# Schematic.net
KiCad netlist of a schematic drawn in EAGLE
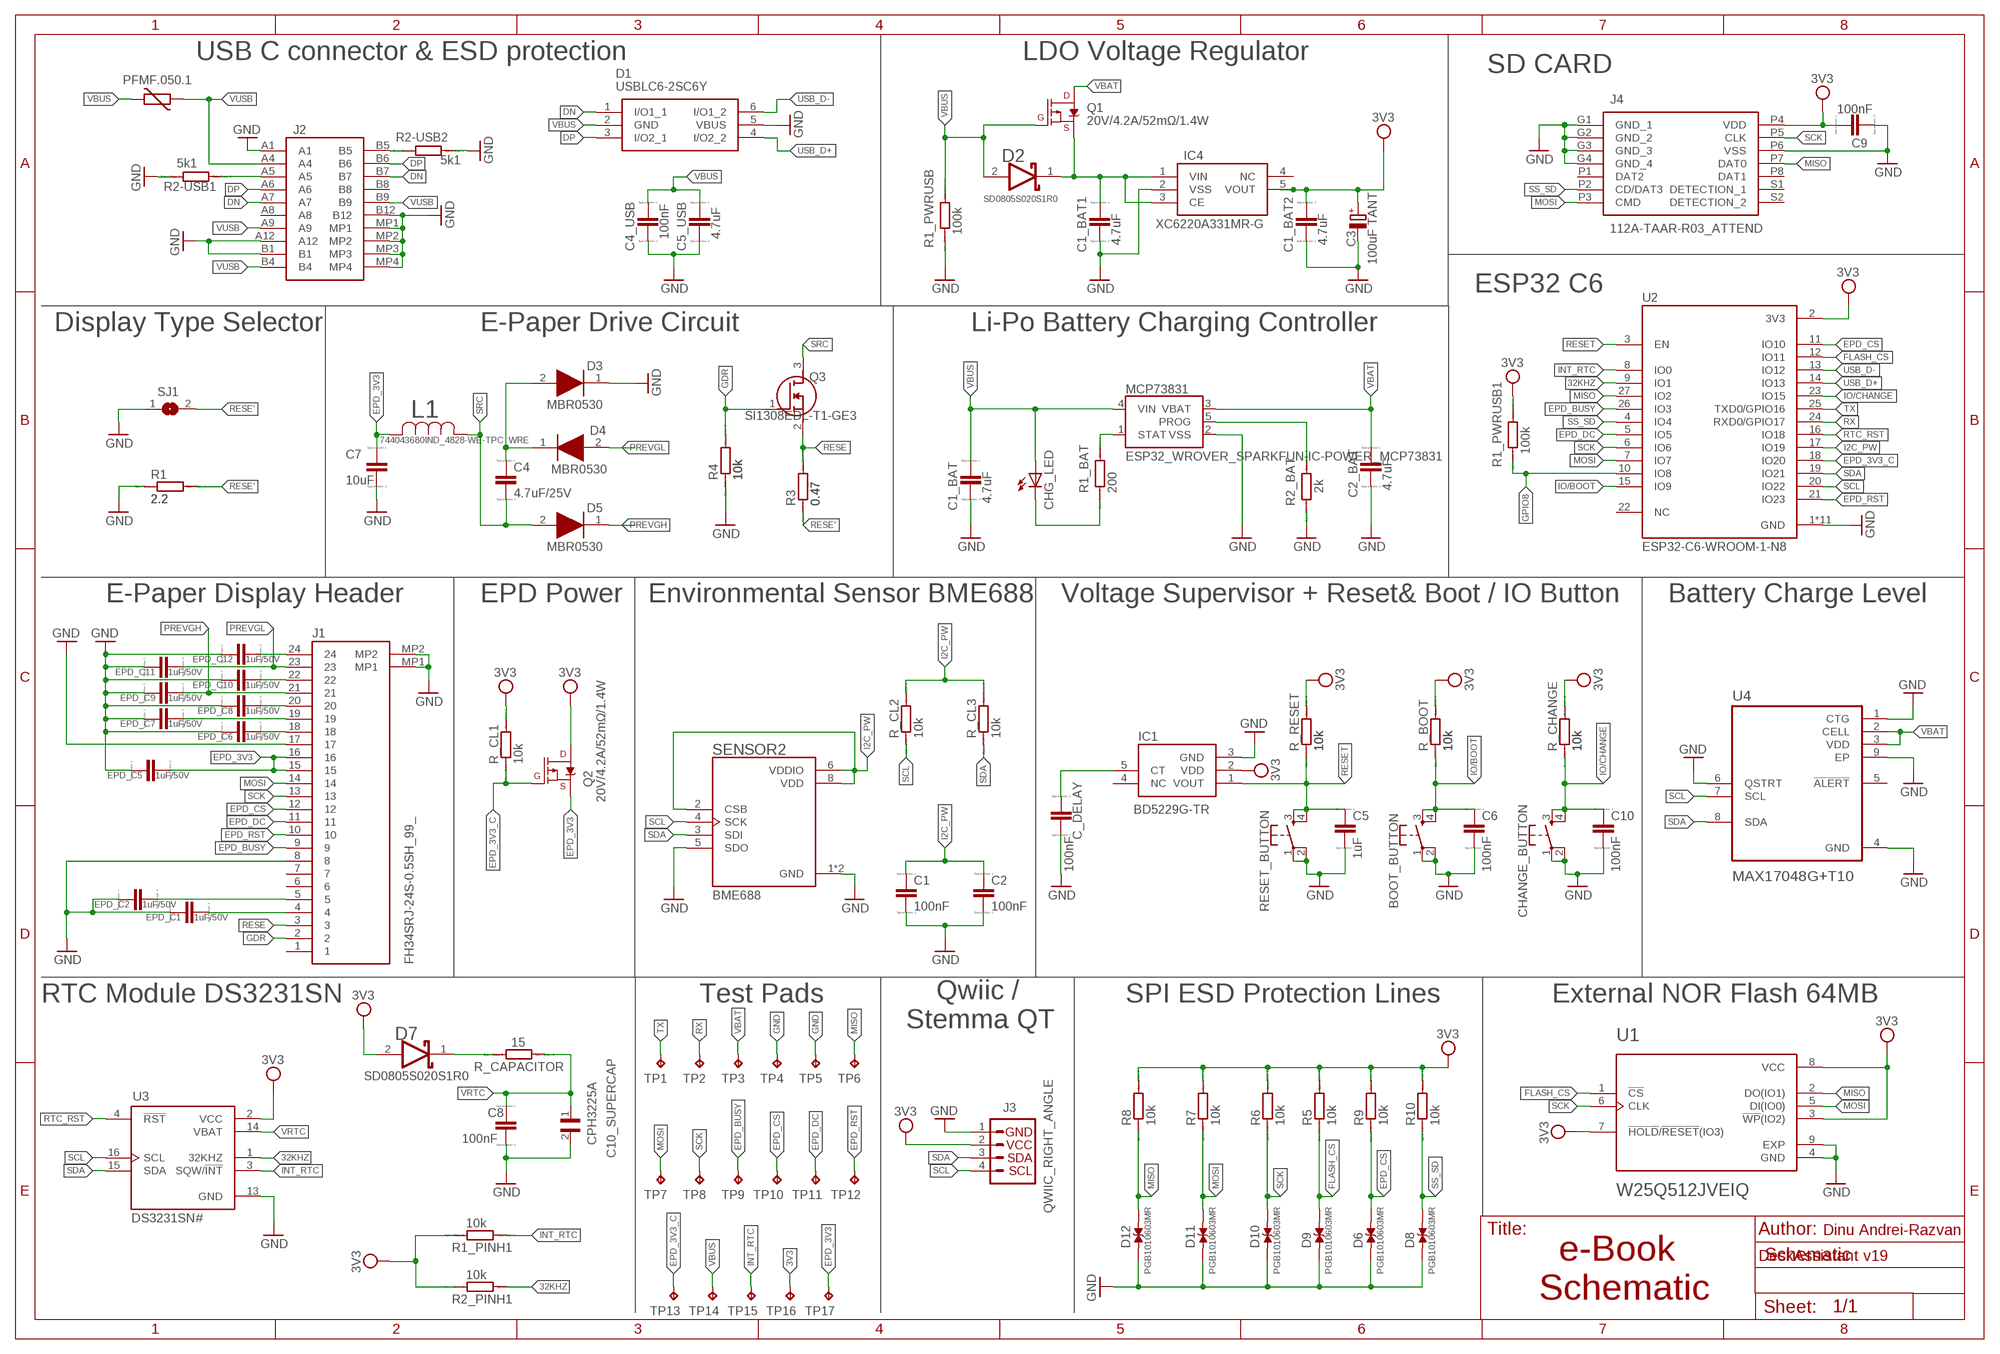
[diagram p0: schematic, sheet 1]

(export (version "E")
  (design (tool "Eeschema 10.0.6"))
  (components
    (comp (ref "BOOT_BUTTON")
      (value "BUTTON_CUSYOMV1")
      (footprint "eagle-import:MYBUTTON")
      (libsource (lib "eagle-import") (part "BUTTON_CUSYOMV1"))
    )
    (comp (ref "C1")
      (value "100nF")
      (footprint "eagle-import:EAGLE-LTSPICE_C0402")
      (libsource (lib "eagle-import") (part "EAGLE-LTSPICE_CC0402"))
    )
    (comp (ref "C1_BAT")
      (value "4.7uF")
      (footprint "eagle-import:EAGLE-LTSPICE_C0402")
      (libsource (lib "eagle-import") (part "EAGLE-LTSPICE_CC0402"))
    )
    (comp (ref "C1_BAT1")
      (value "4.7uF")
      (footprint "eagle-import:EAGLE-LTSPICE_C0402")
      (libsource (lib "eagle-import") (part "EAGLE-LTSPICE_CC0402"))
    )
    (comp (ref "C1_BAT2")
      (value "4.7uF")
      (footprint "eagle-import:EAGLE-LTSPICE_C0402")
      (libsource (lib "eagle-import") (part "EAGLE-LTSPICE_CC0402"))
    )
    (comp (ref "C2")
      (value "100nF")
      (footprint "eagle-import:EAGLE-LTSPICE_C0402")
      (libsource (lib "eagle-import") (part "EAGLE-LTSPICE_CC0402"))
    )
    (comp (ref "C2_BAT")
      (value "4.7uF")
      (footprint "eagle-import:EAGLE-LTSPICE_C0402")
      (libsource (lib "eagle-import") (part "EAGLE-LTSPICE_CC0402"))
    )
    (comp (ref "C3")
      (value "100uF TANT")
      (footprint "eagle-import:RCL_CT3528")
      (libsource (lib "eagle-import") (part "RCL_CPOL-EUCT3528"))
    )
    (comp (ref "C4")
      (value "4.7uF/25V")
      (footprint "eagle-import:EAGLE-LTSPICE_C0402")
      (libsource (lib "eagle-import") (part "EAGLE-LTSPICE_CC0402"))
    )
    (comp (ref "C4_USB")
      (value "100nF")
      (footprint "eagle-import:ESP32_WROVER_EAGLE-LTSPICE_C0402")
      (libsource (lib "eagle-import") (part "ESP32_WROVER_EAGLE-LTSPICE_CC0402"))
    )
    (comp (ref "C5")
      (value "1uF")
      (footprint "eagle-import:EAGLE-LTSPICE_C0402")
      (libsource (lib "eagle-import") (part "EAGLE-LTSPICE_CC0402"))
    )
    (comp (ref "C5_USB")
      (value "4.7uF")
      (footprint "eagle-import:ESP32_WROVER_EAGLE-LTSPICE_C0402")
      (libsource (lib "eagle-import") (part "ESP32_WROVER_EAGLE-LTSPICE_CC0402"))
    )
    (comp (ref "C6")
      (value "100nF")
      (footprint "eagle-import:EAGLE-LTSPICE_C0402")
      (libsource (lib "eagle-import") (part "EAGLE-LTSPICE_CC0402"))
    )
    (comp (ref "C7")
      (value "10uF")
      (footprint "eagle-import:EAGLE-LTSPICE_C0402")
      (libsource (lib "eagle-import") (part "EAGLE-LTSPICE_CC0402"))
    )
    (comp (ref "C8")
      (value "100nF")
      (footprint "eagle-import:EAGLE-LTSPICE_C0402")
      (libsource (lib "eagle-import") (part "EAGLE-LTSPICE_CC0402"))
    )
    (comp (ref "C9")
      (value "100nF")
      (footprint "eagle-import:ESP32_WROVER_EAGLE-LTSPICE_C0402")
      (libsource (lib "eagle-import") (part "ESP32_WROVER_EAGLE-LTSPICE_CC0402"))
    )
    (comp (ref "C10")
      (value "100nF")
      (footprint "eagle-import:EAGLE-LTSPICE_C0402")
      (libsource (lib "eagle-import") (part "EAGLE-LTSPICE_CC0402"))
    )
    (comp (ref "C10_SUPERCAP")
      (value "CPH3225A")
      (footprint "eagle-import:CAPCP3225X100N")
      (fields (field (name "MF") "Seiko Instruments"))
      (libsource (lib "eagle-import") (part "CPH3225A"))
    )
    (comp (ref "CHANGE_BUTTON")
      (value "BUTTON_CUSYOMV1")
      (footprint "eagle-import:MYBUTTON")
      (libsource (lib "eagle-import") (part "BUTTON_CUSYOMV1"))
    )
    (comp (ref "CHG_LED")
      (value "ADAFRUIT_LEDCHIP-LED0603")
      (footprint "eagle-import:ADAFRUIT_CHIP-LED0603")
      (libsource (lib "eagle-import") (part "ADAFRUIT_LEDCHIP-LED0603"))
    )
    (comp (ref "C_DELAY")
      (value "100nF")
      (footprint "eagle-import:EAGLE-LTSPICE_C0402")
      (libsource (lib "eagle-import") (part "EAGLE-LTSPICE_CC0402"))
    )
    (comp (ref "D1")
      (value "USBLC6-2SC6Y")
      (footprint "eagle-import:SOT95P280X145-6N")
      (fields (field (name "MF") "STMicroelectronics"))
      (libsource (lib "eagle-import") (part "USBLC6-2SC6Y"))
    )
    (comp (ref "D2")
      (value "ESP32_WROVER_AVX---SD0805S020S1R0_AVX_SD0805S020S1R0_0_0AVX_SD0805S020S1R0_0_0")
      (footprint "eagle-import:ESP32_WROVER_AVX---SD0805S020S1R0_AVX_SD0805S020S1R0_0")
      (fields
        (field (name "DIGIKEY_PART_NUMBER") "478-7800-1-ND")
        (field (name "MF") "AVX")
        (field (name "MOUSER_PART_NUMBER") "581-SD0805S020S1R0")
      )
      (libsource (lib "eagle-import") (part "ESP32_WROVER_AVX---SD0805S020S1R0_AVX_SD0805S020S1R0_0_0AVX_SD0805S020S1R0_0_0"))
    )
    (comp (ref "D3")
      (value "MBR0530")
      (footprint "eagle-import:SOD3716X135N")
      (fields (field (name "MF") "ON Semiconductor"))
      (libsource (lib "eagle-import") (part "MBR0530"))
    )
    (comp (ref "D4")
      (value "MBR0530")
      (footprint "eagle-import:SOD3716X135N")
      (fields (field (name "MF") "ON Semiconductor"))
      (libsource (lib "eagle-import") (part "MBR0530"))
    )
    (comp (ref "D5")
      (value "MBR0530")
      (footprint "eagle-import:SOD3716X135N")
      (fields (field (name "MF") "ON Semiconductor"))
      (libsource (lib "eagle-import") (part "MBR0530"))
    )
    (comp (ref "D6")
      (value "PGB1010603MR")
      (footprint "eagle-import:DIOC1608X36N")
      (fields (field (name "MF") "Littelfuse Inc."))
      (libsource (lib "eagle-import") (part "PGB1010603MR"))
    )
    (comp (ref "D7")
      (value "ESP32_WROVER_AVX---SD0805S020S1R0_AVX_SD0805S020S1R0_0_0AVX_SD0805S020S1R0_0_0")
      (footprint "eagle-import:ESP32_WROVER_AVX---SD0805S020S1R0_AVX_SD0805S020S1R0_0")
      (fields
        (field (name "DIGIKEY_PART_NUMBER") "478-7800-1-ND")
        (field (name "MF") "AVX")
        (field (name "MOUSER_PART_NUMBER") "581-SD0805S020S1R0")
      )
      (libsource (lib "eagle-import") (part "ESP32_WROVER_AVX---SD0805S020S1R0_AVX_SD0805S020S1R0_0_0AVX_SD0805S020S1R0_0_0"))
    )
    (comp (ref "D8")
      (value "PGB1010603MR")
      (footprint "eagle-import:DIOC1608X36N")
      (fields (field (name "MF") "Littelfuse Inc."))
      (libsource (lib "eagle-import") (part "PGB1010603MR"))
    )
    (comp (ref "D9")
      (value "PGB1010603MR")
      (footprint "eagle-import:DIOC1608X36N")
      (fields (field (name "MF") "Littelfuse Inc."))
      (libsource (lib "eagle-import") (part "PGB1010603MR"))
    )
    (comp (ref "D10")
      (value "PGB1010603MR")
      (footprint "eagle-import:DIOC1608X36N")
      (fields (field (name "MF") "Littelfuse Inc."))
      (libsource (lib "eagle-import") (part "PGB1010603MR"))
    )
    (comp (ref "D11")
      (value "PGB1010603MR")
      (footprint "eagle-import:DIOC1608X36N")
      (fields (field (name "MF") "Littelfuse Inc."))
      (libsource (lib "eagle-import") (part "PGB1010603MR"))
    )
    (comp (ref "D12")
      (value "PGB1010603MR")
      (footprint "eagle-import:DIOC1608X36N")
      (fields (field (name "MF") "Littelfuse Inc."))
      (libsource (lib "eagle-import") (part "PGB1010603MR"))
    )
    (comp (ref "EPD_C1")
      (value "1uF/50V")
      (footprint "eagle-import:EAGLE-LTSPICE_C0402")
      (libsource (lib "eagle-import") (part "EAGLE-LTSPICE_CC0402"))
    )
    (comp (ref "EPD_C2")
      (value "1uF/50V")
      (footprint "eagle-import:EAGLE-LTSPICE_C0402")
      (libsource (lib "eagle-import") (part "EAGLE-LTSPICE_CC0402"))
    )
    (comp (ref "EPD_C5")
      (value "1uF/50V")
      (footprint "eagle-import:EAGLE-LTSPICE_C0402")
      (libsource (lib "eagle-import") (part "EAGLE-LTSPICE_CC0402"))
    )
    (comp (ref "EPD_C6")
      (value "1uF/50V")
      (footprint "eagle-import:EAGLE-LTSPICE_C0402")
      (libsource (lib "eagle-import") (part "EAGLE-LTSPICE_CC0402"))
    )
    (comp (ref "EPD_C7")
      (value "1uF/50V")
      (footprint "eagle-import:EAGLE-LTSPICE_C0402")
      (libsource (lib "eagle-import") (part "EAGLE-LTSPICE_CC0402"))
    )
    (comp (ref "EPD_C8")
      (value "1uF/50V")
      (footprint "eagle-import:EAGLE-LTSPICE_C0402")
      (libsource (lib "eagle-import") (part "EAGLE-LTSPICE_CC0402"))
    )
    (comp (ref "EPD_C9")
      (value "1uF/50V")
      (footprint "eagle-import:EAGLE-LTSPICE_C0402")
      (libsource (lib "eagle-import") (part "EAGLE-LTSPICE_CC0402"))
    )
    (comp (ref "EPD_C10")
      (value "1uF/50V")
      (footprint "eagle-import:EAGLE-LTSPICE_C0402")
      (libsource (lib "eagle-import") (part "EAGLE-LTSPICE_CC0402"))
    )
    (comp (ref "EPD_C11")
      (value "1uF/50V")
      (footprint "eagle-import:EAGLE-LTSPICE_C0402")
      (libsource (lib "eagle-import") (part "EAGLE-LTSPICE_CC0402"))
    )
    (comp (ref "EPD_C12")
      (value "1uF/50V")
      (footprint "eagle-import:EAGLE-LTSPICE_C0402")
      (libsource (lib "eagle-import") (part "EAGLE-LTSPICE_CC0402"))
    )
    (comp (ref "IC1")
      (value "BD5229G-TR")
      (footprint "eagle-import:SOT95P280X125-5N")
      (fields (field (name "MOUSER_PART_NUMBER") "755-BD5229G-TR"))
      (libsource (lib "eagle-import") (part "BD5229G-TR"))
    )
    (comp (ref "IC4")
      (value "XC6220A331MR-G")
      (footprint "eagle-import:SOT95P280X120-5N")
      (fields (field (name "MOUSER_PART_NUMBER") "865-XC6220A331MR-G"))
      (libsource (lib "eagle-import") (part "XC6220A331MR-G"))
    )
    (comp (ref "J1")
      (value "FH34SRJ-24S-0.5SH_99_")
      (footprint "eagle-import:FH34SRJ24S05SH99")
      (fields
        (field (name "MANUFACTURER_PART_NUMBER") "FH34SRJ-24S-0.5SH(99)")
        (field (name "MOUSER_PART_NUMBER") "798-FH34SRJ24S05SH99")
      )
      (libsource (lib "eagle-import") (part "FH34SRJ-24S-0.5SH_99_"))
    )
    (comp (ref "J2")
      (value "SAMACSYS_PARTS_USB4110-GF-A")
      (footprint "eagle-import:SAMACSYS_PARTS_USB4110GFA")
      (fields
        (field (name "MANUFACTURER_PART_NUMBER") "USB4110-GF-A")
        (field (name "MOUSER_PART_NUMBER") "640-USB4110-GF-A")
      )
      (libsource (lib "eagle-import") (part "SAMACSYS_PARTS_USB4110-GF-A"))
    )
    (comp (ref "J3")
      (value "QWIIC_RIGHT_ANGLE")
      (footprint "eagle-import:JST04_1MM_RA")
      (libsource (lib "eagle-import") (part "QWIIC_CONNECTORJS-1MM"))
    )
    (comp (ref "J4")
      (value "112A-TAAR-R03_ATTEND")
      (footprint "eagle-import:112ATAARR03ATTEND")
      (fields (field (name "MANUFACTURER_PART_NUMBER") "112A-TAAR-R03 ATTEND"))
      (libsource (lib "eagle-import") (part "112A-TAAR-R03_ATTEND"))
    )
    (comp (ref "L1")
      (value "744043680IND_4828-WE-TPC_WRE")
      (footprint "eagle-import:IND_4828-WE-TPC_WRE")
      (fields
        (field (name "MANUFACTURER_PART_NUMBER") "744043680")
        (field (name "COPYRIGHT") "Copyright (C) 2024 Ultra Librarian. All rights reserved.")
      )
      (libsource (lib "eagle-import") (part "744043680IND_4828-WE-TPC_WRE"))
    )
    (comp (ref "MCP73831")
      (value "ESP32_WROVER_SPARKFUN-IC-POWER_MCP73831")
      (footprint "eagle-import:ESP32_WROVER_SPARKFUN-IC-POWER_SOT23-5")
      (libsource (lib "eagle-import") (part "ESP32_WROVER_SPARKFUN-IC-POWER_MCP73831"))
    )
    (comp (ref "PFMF.050.1")
      (value "ESP32C6_VARISTORCN1812")
      (footprint "eagle-import:ESP32C6_VARISTOR_CT_CN1812")
      (libsource (lib "eagle-import") (part "ESP32C6_VARISTORCN1812"))
    )
    (comp (ref "Q1")
      (value "20V/4.2A/52mΩ/1.4W")
      (footprint "eagle-import:ESP32_WROVER_SPARKFUN-DISCRETESEMI_SOT23-3")
      (libsource (lib "eagle-import") (part "ESP32_WROVER_SPARKFUN-DISCRETESEMI_MOSFET_PCH-DMG2305UX-7"))
    )
    (comp (ref "Q2")
      (value "20V/4.2A/52mΩ/1.4W")
      (footprint "eagle-import:ESP32_WROVER_SPARKFUN-DISCRETESEMI_SOT23-3")
      (libsource (lib "eagle-import") (part "ESP32_WROVER_SPARKFUN-DISCRETESEMI_MOSFET_PCH-DMG2305UX-7"))
    )
    (comp (ref "Q3")
      (value "SI1308EDL-T1-GE3")
      (footprint "eagle-import:SOT65P210X110-3N")
      (fields (field (name "MF") "Vishay Siliconix"))
      (libsource (lib "eagle-import") (part "SI1308EDL-T1-GE3"))
    )
    (comp (ref "R1")
      (value "2.2")
      (footprint "eagle-import:ESP32_WROVER_EAGLE-LTSPICE_R0402")
      (libsource (lib "eagle-import") (part "ESP32_WROVER_EAGLE-LTSPICE_RR0402"))
    )
    (comp (ref "R1_BAT")
      (value "200")
      (footprint "eagle-import:ESP32_WROVER_EAGLE-LTSPICE_R0402")
      (libsource (lib "eagle-import") (part "ESP32_WROVER_EAGLE-LTSPICE_RR0402"))
    )
    (comp (ref "R1_PINH1")
      (value "10k")
      (footprint "eagle-import:ESP32_WROVER_EAGLE-LTSPICE_R0402")
      (libsource (lib "eagle-import") (part "ESP32_WROVER_EAGLE-LTSPICE_RR0402"))
    )
    (comp (ref "R1_PWRUSB")
      (value "100k")
      (footprint "eagle-import:ESP32_WROVER_EAGLE-LTSPICE_R0402")
      (libsource (lib "eagle-import") (part "ESP32_WROVER_EAGLE-LTSPICE_RR0402"))
    )
    (comp (ref "R1_PWRUSB1")
      (value "100k")
      (footprint "eagle-import:ESP32_WROVER_EAGLE-LTSPICE_R0402")
      (libsource (lib "eagle-import") (part "ESP32_WROVER_EAGLE-LTSPICE_RR0402"))
    )
    (comp (ref "R2-USB1")
      (value "5k1")
      (footprint "eagle-import:ESP32_WROVER_EAGLE-LTSPICE_R0402")
      (libsource (lib "eagle-import") (part "ESP32_WROVER_EAGLE-LTSPICE_RR0402"))
    )
    (comp (ref "R2-USB2")
      (value "5k1")
      (footprint "eagle-import:ESP32_WROVER_EAGLE-LTSPICE_R0402")
      (libsource (lib "eagle-import") (part "ESP32_WROVER_EAGLE-LTSPICE_RR0402"))
    )
    (comp (ref "R2_BAT")
      (value "2k")
      (footprint "eagle-import:ESP32_WROVER_EAGLE-LTSPICE_R0402")
      (libsource (lib "eagle-import") (part "ESP32_WROVER_EAGLE-LTSPICE_RR0402"))
    )
    (comp (ref "R2_PINH1")
      (value "10k")
      (footprint "eagle-import:ESP32_WROVER_EAGLE-LTSPICE_R0402")
      (libsource (lib "eagle-import") (part "ESP32_WROVER_EAGLE-LTSPICE_RR0402"))
    )
    (comp (ref "R3")
      (value "0.47")
      (footprint "eagle-import:ESP32_WROVER_EAGLE-LTSPICE_R0402")
      (libsource (lib "eagle-import") (part "ESP32_WROVER_EAGLE-LTSPICE_RR0402"))
    )
    (comp (ref "R4")
      (value "10k")
      (footprint "eagle-import:ESP32_WROVER_EAGLE-LTSPICE_R0402")
      (libsource (lib "eagle-import") (part "ESP32_WROVER_EAGLE-LTSPICE_RR0402"))
    )
    (comp (ref "R5")
      (value "10k")
      (footprint "eagle-import:ESP32_WROVER_EAGLE-LTSPICE_R0402")
      (libsource (lib "eagle-import") (part "ESP32_WROVER_EAGLE-LTSPICE_RR0402"))
    )
    (comp (ref "R6")
      (value "10k")
      (footprint "eagle-import:ESP32_WROVER_EAGLE-LTSPICE_R0402")
      (libsource (lib "eagle-import") (part "ESP32_WROVER_EAGLE-LTSPICE_RR0402"))
    )
    (comp (ref "R7")
      (value "10k")
      (footprint "eagle-import:ESP32_WROVER_EAGLE-LTSPICE_R0402")
      (libsource (lib "eagle-import") (part "ESP32_WROVER_EAGLE-LTSPICE_RR0402"))
    )
    (comp (ref "R8")
      (value "10k")
      (footprint "eagle-import:ESP32_WROVER_EAGLE-LTSPICE_R0402")
      (libsource (lib "eagle-import") (part "ESP32_WROVER_EAGLE-LTSPICE_RR0402"))
    )
    (comp (ref "R9")
      (value "10k")
      (footprint "eagle-import:ESP32_WROVER_EAGLE-LTSPICE_R0402")
      (libsource (lib "eagle-import") (part "ESP32_WROVER_EAGLE-LTSPICE_RR0402"))
    )
    (comp (ref "R10")
      (value "10k")
      (footprint "eagle-import:ESP32_WROVER_EAGLE-LTSPICE_R0402")
      (libsource (lib "eagle-import") (part "ESP32_WROVER_EAGLE-LTSPICE_RR0402"))
    )
    (comp (ref "RESET_BUTTON")
      (value "BUTTON_CUSYOMV1")
      (footprint "eagle-import:MYBUTTON")
      (libsource (lib "eagle-import") (part "BUTTON_CUSYOMV1"))
    )
    (comp (ref "R_BOOT")
      (value "10k")
      (footprint "eagle-import:ESP32_WROVER_EAGLE-LTSPICE_R0402")
      (libsource (lib "eagle-import") (part "ESP32_WROVER_EAGLE-LTSPICE_RR0402"))
    )
    (comp (ref "R_CAPACITOR")
      (value "15")
      (footprint "eagle-import:ESP32_WROVER_EAGLE-LTSPICE_R0402")
      (libsource (lib "eagle-import") (part "ESP32_WROVER_EAGLE-LTSPICE_RR0402"))
    )
    (comp (ref "R_CHANGE")
      (value "10k")
      (footprint "eagle-import:ESP32_WROVER_EAGLE-LTSPICE_R0402")
      (libsource (lib "eagle-import") (part "ESP32_WROVER_EAGLE-LTSPICE_RR0402"))
    )
    (comp (ref "R_CL1")
      (value "10k")
      (footprint "eagle-import:ESP32_WROVER_EAGLE-LTSPICE_R0402")
      (libsource (lib "eagle-import") (part "ESP32_WROVER_EAGLE-LTSPICE_RR0402"))
    )
    (comp (ref "R_CL2")
      (value "10k")
      (footprint "eagle-import:ESP32_WROVER_EAGLE-LTSPICE_R0402")
      (libsource (lib "eagle-import") (part "ESP32_WROVER_EAGLE-LTSPICE_RR0402"))
    )
    (comp (ref "R_CL3")
      (value "10k")
      (footprint "eagle-import:ESP32_WROVER_EAGLE-LTSPICE_R0402")
      (libsource (lib "eagle-import") (part "ESP32_WROVER_EAGLE-LTSPICE_RR0402"))
    )
    (comp (ref "R_RESET")
      (value "10k")
      (footprint "eagle-import:ESP32_WROVER_EAGLE-LTSPICE_R0402")
      (libsource (lib "eagle-import") (part "ESP32_WROVER_EAGLE-LTSPICE_RR0402"))
    )
    (comp (ref "SENSOR2")
      (value "ESP32_WROVER_BME680_BME680")
      (footprint "eagle-import:ESP32_WROVER_BME680_PSON80P300X300X100-8N")
      (fields (field (name "MF") "Bosch Sensortec") (field (name "MP") "BME680"))
      (libsource (lib "eagle-import") (part "ESP32_WROVER_BME680_BME680"))
    )
    (comp (ref "SJ1") (value "SJ") (footprint "eagle-import:SJ") (libsource (lib "eagle-import") (part "SJ")))
    (comp (ref "TP1")
      (value "TPTP20R")
      (footprint "eagle-import:TP20R")
      (libsource (lib "eagle-import") (part "TPTP20R"))
    )
    (comp (ref "TP2")
      (value "TPTP20R")
      (footprint "eagle-import:TP20R")
      (libsource (lib "eagle-import") (part "TPTP20R"))
    )
    (comp (ref "TP3")
      (value "TPTP20R")
      (footprint "eagle-import:TP20R")
      (libsource (lib "eagle-import") (part "TPTP20R"))
    )
    (comp (ref "TP4")
      (value "TPTP20R")
      (footprint "eagle-import:TP20R")
      (libsource (lib "eagle-import") (part "TPTP20R"))
    )
    (comp (ref "TP5")
      (value "TPTP20R")
      (footprint "eagle-import:TP20R")
      (libsource (lib "eagle-import") (part "TPTP20R"))
    )
    (comp (ref "TP6")
      (value "TPTP20R")
      (footprint "eagle-import:TP20R")
      (libsource (lib "eagle-import") (part "TPTP20R"))
    )
    (comp (ref "TP7")
      (value "TPTP20R")
      (footprint "eagle-import:TP20R")
      (libsource (lib "eagle-import") (part "TPTP20R"))
    )
    (comp (ref "TP8")
      (value "TPTP20R")
      (footprint "eagle-import:TP20R")
      (libsource (lib "eagle-import") (part "TPTP20R"))
    )
    (comp (ref "TP9")
      (value "TPTP20R")
      (footprint "eagle-import:TP20R")
      (libsource (lib "eagle-import") (part "TPTP20R"))
    )
    (comp (ref "TP10")
      (value "TPTP20R")
      (footprint "eagle-import:TP20R")
      (libsource (lib "eagle-import") (part "TPTP20R"))
    )
    (comp (ref "TP11")
      (value "TPTP20R")
      (footprint "eagle-import:TP20R")
      (libsource (lib "eagle-import") (part "TPTP20R"))
    )
    (comp (ref "TP12")
      (value "TPTP20R")
      (footprint "eagle-import:TP20R")
      (libsource (lib "eagle-import") (part "TPTP20R"))
    )
    (comp (ref "TP13")
      (value "TPTP20R")
      (footprint "eagle-import:TP20R")
      (libsource (lib "eagle-import") (part "TPTP20R"))
    )
    (comp (ref "TP14")
      (value "TPTP20R")
      (footprint "eagle-import:TP20R")
      (libsource (lib "eagle-import") (part "TPTP20R"))
    )
    (comp (ref "TP15")
      (value "TPTP20R")
      (footprint "eagle-import:TP20R")
      (libsource (lib "eagle-import") (part "TPTP20R"))
    )
    (comp (ref "TP16")
      (value "TPTP20R")
      (footprint "eagle-import:TP20R")
      (libsource (lib "eagle-import") (part "TPTP20R"))
    )
    (comp (ref "TP17")
      (value "TPTP20R")
      (footprint "eagle-import:TP20R")
      (libsource (lib "eagle-import") (part "TPTP20R"))
    )
    (comp (ref "U1")
      (value "W25Q512JVEIQ")
      (footprint "eagle-import:SON127P600X800X80-9N")
      (fields (field (name "MF") "Winbond Electronics"))
      (libsource (lib "eagle-import") (part "W25Q512JVEIQ"))
    )
    (comp (ref "U2")
      (value "ESP32-C6-WROOM-1-N8")
      (footprint "eagle-import:XCVR_ESP32-C6-WROOM-1-N8")
      (fields (field (name "MF") "Espressif Systems"))
      (libsource (lib "eagle-import") (part "ESP32-C6-WROOM-1-N8"))
    )
    (comp (ref "U3")
      (value "DS3231SN#")
      (footprint "eagle-import:SOIC127P1032X265-16N")
      (fields (field (name "MF") "Analog Devices"))
      (libsource (lib "eagle-import") (part "DS3231SN#"))
    )
    (comp (ref "U4")
      (value "MAX17048G+T10")
      (footprint "eagle-import:SON50P200X200X80-9N")
      (fields (field (name "MF") "Analog Devices"))
      (libsource (lib "eagle-import") (part "MAX17048G+T10"))
    )
  )
  (nets
    (net (code "1") (name "3V3") (class "Default")
      (node (ref "C1_BAT2") (pin "1") (pinfunction "1_1") (pintype "passive"))
      (node (ref "C3") (pin "+") (pinfunction "+_+") (pintype "passive"))
      (node (ref "C9") (pin "1") (pinfunction "1_1") (pintype "passive"))
      (node (ref "D7") (pin "2") (pinfunction "ANODE_2") (pintype "bidirectional"))
      (node (ref "IC1") (pin "2") (pinfunction "VDD_2") (pintype "bidirectional"))
      (node (ref "IC4") (pin "5") (pinfunction "VOUT_5") (pintype "bidirectional"))
      (node (ref "J3") (pin "2") (pinfunction "2_2") (pintype "power_in"))
      (node (ref "J4") (pin "P4") (pinfunction "VDD_P4") (pintype "bidirectional"))
      (node (ref "Q2") (pin "3") (pinfunction "D_3") (pintype "bidirectional"))
      (node (ref "R10") (pin "2") (pinfunction "2_2") (pintype "passive"))
      (node (ref "R1_PINH1") (pin "2") (pinfunction "2_2") (pintype "passive"))
      (node (ref "R1_PWRUSB1") (pin "2") (pinfunction "2_2") (pintype "passive"))
      (node (ref "R2_PINH1") (pin "2") (pinfunction "2_2") (pintype "passive"))
      (node (ref "R5") (pin "2") (pinfunction "2_2") (pintype "passive"))
      (node (ref "R6") (pin "2") (pinfunction "2_2") (pintype "passive"))
      (node (ref "R7") (pin "2") (pinfunction "2_2") (pintype "passive"))
      (node (ref "R8") (pin "2") (pinfunction "2_2") (pintype "passive"))
      (node (ref "R9") (pin "2") (pinfunction "2_2") (pintype "passive"))
      (node (ref "R_BOOT") (pin "2") (pinfunction "2_2") (pintype "passive"))
      (node (ref "R_CHANGE") (pin "2") (pinfunction "2_2") (pintype "passive"))
      (node (ref "R_CL1") (pin "2") (pinfunction "2_2") (pintype "passive"))
      (node (ref "R_RESET") (pin "2") (pinfunction "2_2") (pintype "passive"))
      (node (ref "TP16") (pin "TP") (pinfunction "TP_TP") (pintype "input"))
      (node (ref "U1") (pin "3") (pinfunction "~{WP}(IO2)_3") (pintype "bidirectional"))
      (node (ref "U1") (pin "7") (pinfunction "~{HOLD}/~{RESET}(IO3)_7") (pintype "bidirectional"))
      (node (ref "U1") (pin "8") (pinfunction "VCC_8") (pintype "power_in"))
      (node (ref "U2") (pin "2") (pinfunction "3V3_2") (pintype "power_in"))
      (node (ref "U3") (pin "2") (pinfunction "VCC_2") (pintype "power_in"))
    )
    (net (code "2") (name "32KHZ") (class "Default")
      (node (ref "R2_PINH1") (pin "1") (pinfunction "1_1") (pintype "passive"))
      (node (ref "U2") (pin "9") (pinfunction "IO1_9") (pintype "bidirectional"))
      (node (ref "U3") (pin "1") (pinfunction "32KHZ_1") (pintype "output"))
    )
    (net (code "3") (name "DN") (class "Default")
      (node (ref "D1") (pin "1") (pinfunction "I/O1_1_1") (pintype "bidirectional"))
      (node (ref "J2") (pin "A7") (pinfunction "A7_A7") (pintype "bidirectional"))
      (node (ref "J2") (pin "B7") (pinfunction "B7_B7") (pintype "bidirectional"))
    )
    (net (code "4") (name "DP") (class "Default")
      (node (ref "D1") (pin "3") (pinfunction "I/O2_1_3") (pintype "bidirectional"))
      (node (ref "J2") (pin "A6") (pinfunction "A6_A6") (pintype "bidirectional"))
      (node (ref "J2") (pin "B6") (pinfunction "B6_B6") (pintype "bidirectional"))
    )
    (net (code "5") (name "EPD_3V3") (class "Default")
      (node (ref "C7") (pin "1") (pinfunction "1_1") (pintype "passive"))
      (node (ref "EPD_C5") (pin "2") (pinfunction "2_2") (pintype "passive"))
      (node (ref "J1") (pin "15") (pinfunction "15_15") (pintype "bidirectional"))
      (node (ref "J1") (pin "16") (pinfunction "16_16") (pintype "bidirectional"))
      (node (ref "L1") (pin "2") (pinfunction "2_2") (pintype "passive"))
      (node (ref "Q2") (pin "2") (pinfunction "S_2") (pintype "bidirectional"))
      (node (ref "TP17") (pin "TP") (pinfunction "TP_TP") (pintype "input"))
    )
    (net (code "6") (name "EPD_3V3_C") (class "Default")
      (node (ref "Q2") (pin "1") (pinfunction "G_1") (pintype "bidirectional"))
      (node (ref "R_CL1") (pin "1") (pinfunction "1_1") (pintype "passive"))
      (node (ref "TP13") (pin "TP") (pinfunction "TP_TP") (pintype "input"))
      (node (ref "U2") (pin "18") (pinfunction "IO20_18") (pintype "bidirectional"))
    )
    (net (code "7") (name "EPD_BUSY") (class "Default")
      (node (ref "J1") (pin "9") (pinfunction "9_9") (pintype "bidirectional"))
      (node (ref "TP9") (pin "TP") (pinfunction "TP_TP") (pintype "input"))
      (node (ref "U2") (pin "26") (pinfunction "IO3_26") (pintype "bidirectional"))
    )
    (net (code "8") (name "EPD_CS") (class "Default")
      (node (ref "D6") (pin "2") (pinfunction "2_2") (pintype "passive"))
      (node (ref "J1") (pin "12") (pinfunction "12_12") (pintype "bidirectional"))
      (node (ref "R9") (pin "1") (pinfunction "1_1") (pintype "passive"))
      (node (ref "TP10") (pin "TP") (pinfunction "TP_TP") (pintype "input"))
      (node (ref "U2") (pin "11") (pinfunction "IO10_11") (pintype "bidirectional"))
    )
    (net (code "9") (name "EPD_DC") (class "Default")
      (node (ref "J1") (pin "11") (pinfunction "11_11") (pintype "bidirectional"))
      (node (ref "TP11") (pin "TP") (pinfunction "TP_TP") (pintype "input"))
      (node (ref "U2") (pin "5") (pinfunction "IO5_5") (pintype "bidirectional"))
    )
    (net (code "10") (name "EPD_RST") (class "Default")
      (node (ref "J1") (pin "10") (pinfunction "10_10") (pintype "bidirectional"))
      (node (ref "TP12") (pin "TP") (pinfunction "TP_TP") (pintype "input"))
      (node (ref "U2") (pin "21") (pinfunction "IO23_21") (pintype "bidirectional"))
    )
    (net (code "11") (name "FLASH_CS") (class "Default")
      (node (ref "D9") (pin "2") (pinfunction "2_2") (pintype "passive"))
      (node (ref "R5") (pin "1") (pinfunction "1_1") (pintype "passive"))
      (node (ref "U1") (pin "1") (pinfunction "~{CS}_1") (pintype "input"))
      (node (ref "U2") (pin "12") (pinfunction "IO11_12") (pintype "bidirectional"))
    )
    (net (code "12") (name "GDR") (class "Default")
      (node (ref "J1") (pin "2") (pinfunction "2_2") (pintype "bidirectional"))
      (node (ref "Q3") (pin "1") (pinfunction "G_1") (pintype "bidirectional"))
      (node (ref "R4") (pin "2") (pinfunction "2_2") (pintype "passive"))
    )
    (net (code "13") (name "GND") (class "Default")
      (node (ref "BOOT_BUTTON") (pin "1") (pinfunction "1_1") (pintype "passive"))
      (node (ref "BOOT_BUTTON") (pin "2") (pinfunction "2_2") (pintype "passive"))
      (node (ref "C1") (pin "2") (pinfunction "2_2") (pintype "passive"))
      (node (ref "C10") (pin "2") (pinfunction "2_2") (pintype "passive"))
      (node (ref "C10_SUPERCAP") (pin "2") (pinfunction "2_2") (pintype "passive"))
      (node (ref "C1_BAT") (pin "2") (pinfunction "2_2") (pintype "passive"))
      (node (ref "C1_BAT1") (pin "2") (pinfunction "2_2") (pintype "passive"))
      (node (ref "C1_BAT2") (pin "2") (pinfunction "2_2") (pintype "passive"))
      (node (ref "C2") (pin "2") (pinfunction "2_2") (pintype "passive"))
      (node (ref "C2_BAT") (pin "2") (pinfunction "2_2") (pintype "passive"))
      (node (ref "C3") (pin "-") (pinfunction "-_-") (pintype "passive"))
      (node (ref "C4_USB") (pin "2") (pinfunction "2_2") (pintype "passive"))
      (node (ref "C5") (pin "2") (pinfunction "2_2") (pintype "passive"))
      (node (ref "C5_USB") (pin "2") (pinfunction "2_2") (pintype "passive"))
      (node (ref "C6") (pin "2") (pinfunction "2_2") (pintype "passive"))
      (node (ref "C7") (pin "2") (pinfunction "2_2") (pintype "passive"))
      (node (ref "C8") (pin "2") (pinfunction "2_2") (pintype "passive"))
      (node (ref "C9") (pin "2") (pinfunction "2_2") (pintype "passive"))
      (node (ref "CHANGE_BUTTON") (pin "1") (pinfunction "1_1") (pintype "passive"))
      (node (ref "CHANGE_BUTTON") (pin "2") (pinfunction "2_2") (pintype "passive"))
      (node (ref "C_DELAY") (pin "2") (pinfunction "2_2") (pintype "passive"))
      (node (ref "D1") (pin "5") (pinfunction "VBUS_5") (pintype "bidirectional"))
      (node (ref "D10") (pin "1") (pinfunction "1_1") (pintype "passive"))
      (node (ref "D11") (pin "1") (pinfunction "1_1") (pintype "passive"))
      (node (ref "D12") (pin "1") (pinfunction "1_1") (pintype "passive"))
      (node (ref "D3") (pin "1") (pinfunction "K_1") (pintype "bidirectional"))
      (node (ref "D6") (pin "1") (pinfunction "1_1") (pintype "passive"))
      (node (ref "D8") (pin "1") (pinfunction "1_1") (pintype "passive"))
      (node (ref "D9") (pin "1") (pinfunction "1_1") (pintype "passive"))
      (node (ref "EPD_C1") (pin "1") (pinfunction "1_1") (pintype "passive"))
      (node (ref "EPD_C10") (pin "1") (pinfunction "1_1") (pintype "passive"))
      (node (ref "EPD_C11") (pin "1") (pinfunction "1_1") (pintype "passive"))
      (node (ref "EPD_C12") (pin "1") (pinfunction "1_1") (pintype "passive"))
      (node (ref "EPD_C2") (pin "1") (pinfunction "1_1") (pintype "passive"))
      (node (ref "EPD_C5") (pin "1") (pinfunction "1_1") (pintype "passive"))
      (node (ref "EPD_C6") (pin "1") (pinfunction "1_1") (pintype "passive"))
      (node (ref "EPD_C7") (pin "1") (pinfunction "1_1") (pintype "passive"))
      (node (ref "EPD_C8") (pin "1") (pinfunction "1_1") (pintype "passive"))
      (node (ref "EPD_C9") (pin "1") (pinfunction "1_1") (pintype "passive"))
      (node (ref "IC1") (pin "3") (pinfunction "GND_3") (pintype "bidirectional"))
      (node (ref "IC4") (pin "2") (pinfunction "VSS_2") (pintype "bidirectional"))
      (node (ref "J1") (pin "17") (pinfunction "17_17") (pintype "bidirectional"))
      (node (ref "J1") (pin "8") (pinfunction "8_8") (pintype "bidirectional"))
      (node (ref "J1") (pin "MP1") (pinfunction "MP1_MP1") (pintype "bidirectional"))
      (node (ref "J1") (pin "MP2") (pinfunction "MP2_MP2") (pintype "bidirectional"))
      (node (ref "J2") (pin "A1") (pinfunction "A1_A1") (pintype "bidirectional"))
      (node (ref "J2") (pin "A12") (pinfunction "A12_A12") (pintype "bidirectional"))
      (node (ref "J2") (pin "B1") (pinfunction "B1_B1") (pintype "bidirectional"))
      (node (ref "J2") (pin "B12") (pinfunction "B12_B12") (pintype "bidirectional"))
      (node (ref "J2") (pin "MP1") (pinfunction "MP1_MP1") (pintype "bidirectional"))
      (node (ref "J2") (pin "MP2") (pinfunction "MP2_MP2") (pintype "bidirectional"))
      (node (ref "J2") (pin "MP3") (pinfunction "MP3_MP3") (pintype "bidirectional"))
      (node (ref "J2") (pin "MP4") (pinfunction "MP4_MP4") (pintype "bidirectional"))
      (node (ref "J3") (pin "1") (pinfunction "1_1") (pintype "power_in"))
      (node (ref "J4") (pin "G1") (pinfunction "GND_1_G1") (pintype "bidirectional"))
      (node (ref "J4") (pin "G2") (pinfunction "GND_2_G2") (pintype "bidirectional"))
      (node (ref "J4") (pin "G3") (pinfunction "GND_3_G3") (pintype "bidirectional"))
      (node (ref "J4") (pin "G4") (pinfunction "GND_4_G4") (pintype "bidirectional"))
      (node (ref "J4") (pin "P6") (pinfunction "VSS_P6") (pintype "bidirectional"))
      (node (ref "MCP73831") (pin "2") (pinfunction "VSS_2") (pintype "power_in"))
      (node (ref "R1") (pin "1") (pinfunction "1_1") (pintype "passive"))
      (node (ref "R1_PWRUSB") (pin "1") (pinfunction "1_1") (pintype "passive"))
      (node (ref "R2-USB1") (pin "1") (pinfunction "1_1") (pintype "passive"))
      (node (ref "R2-USB2") (pin "1") (pinfunction "1_1") (pintype "passive"))
      (node (ref "R2_BAT") (pin "1") (pinfunction "1_1") (pintype "passive"))
      (node (ref "R4") (pin "1") (pinfunction "1_1") (pintype "passive"))
      (node (ref "RESET_BUTTON") (pin "1") (pinfunction "1_1") (pintype "passive"))
      (node (ref "RESET_BUTTON") (pin "2") (pinfunction "2_2") (pintype "passive"))
      (node (ref "SENSOR2") (pin "1") (pinfunction "GND_1") (pintype "power_in"))
      (node (ref "SENSOR2") (pin "5") (pinfunction "SDO_5") (pintype "bidirectional"))
      (node (ref "SENSOR2") (pin "7") (pinfunction "GND_7") (pintype "power_in"))
      (node (ref "SJ1") (pin "1") (pinfunction "1_1") (pintype "passive"))
      (node (ref "TP4") (pin "TP") (pinfunction "TP_TP") (pintype "input"))
      (node (ref "TP5") (pin "TP") (pinfunction "TP_TP") (pintype "input"))
      (node (ref "U1") (pin "4") (pinfunction "GND_4") (pintype "power_in"))
      (node (ref "U1") (pin "9") (pinfunction "EXP_9") (pintype "passive"))
      (node (ref "U2") (pin "1") (pinfunction "GND_1") (pintype "power_in"))
      (node (ref "U2") (pin "28") (pinfunction "GND_28") (pintype "power_in"))
      (node (ref "U2") (pin "29_1") (pinfunction "GND_29_1") (pintype "power_in"))
      (node (ref "U2") (pin "29_2") (pinfunction "GND_29_2") (pintype "power_in"))
      (node (ref "U2") (pin "29_3") (pinfunction "GND_29_3") (pintype "power_in"))
      (node (ref "U2") (pin "29_4") (pinfunction "GND_29_4") (pintype "power_in"))
      (node (ref "U2") (pin "29_5") (pinfunction "GND_29_5") (pintype "power_in"))
      (node (ref "U2") (pin "29_6") (pinfunction "GND_29_6") (pintype "power_in"))
      (node (ref "U2") (pin "29_7") (pinfunction "GND_29_7") (pintype "power_in"))
      (node (ref "U2") (pin "29_8") (pinfunction "GND_29_8") (pintype "power_in"))
      (node (ref "U2") (pin "29_9") (pinfunction "GND_29_9") (pintype "power_in"))
      (node (ref "U3") (pin "13") (pinfunction "GND_13") (pintype "power_in"))
      (node (ref "U4") (pin "1") (pinfunction "CTG_1") (pintype "power_in"))
      (node (ref "U4") (pin "4") (pinfunction "GND_4") (pintype "power_in"))
      (node (ref "U4") (pin "6") (pinfunction "QSTRT_6") (pintype "input"))
      (node (ref "U4") (pin "9") (pinfunction "EP_9") (pintype "power_in"))
    )
    (net (code "14") (name "GPIO8") (class "Default")
      (node (ref "R1_PWRUSB1") (pin "1") (pinfunction "1_1") (pintype "passive"))
      (node (ref "U2") (pin "10") (pinfunction "IO8_10") (pintype "bidirectional"))
    )
    (net (code "15") (name "I2C_PW") (class "Default")
      (node (ref "C1") (pin "1") (pinfunction "1_1") (pintype "passive"))
      (node (ref "C2") (pin "1") (pinfunction "1_1") (pintype "passive"))
      (node (ref "R_CL2") (pin "2") (pinfunction "2_2") (pintype "passive"))
      (node (ref "R_CL3") (pin "2") (pinfunction "2_2") (pintype "passive"))
      (node (ref "SENSOR2") (pin "2") (pinfunction "CSB_2") (pintype "input"))
      (node (ref "SENSOR2") (pin "6") (pinfunction "VDDIO_6") (pintype "power_in"))
      (node (ref "SENSOR2") (pin "8") (pinfunction "VDD_8") (pintype "power_in"))
      (node (ref "U2") (pin "17") (pinfunction "IO19_17") (pintype "bidirectional"))
    )
    (net (code "16") (name "INT_RTC") (class "Default")
      (node (ref "R1_PINH1") (pin "1") (pinfunction "1_1") (pintype "passive"))
      (node (ref "TP15") (pin "TP") (pinfunction "TP_TP") (pintype "input"))
      (node (ref "U2") (pin "8") (pinfunction "IO0_8") (pintype "bidirectional"))
      (node (ref "U3") (pin "3") (pinfunction "SQW/~{INT}_3") (pintype "output"))
    )
    (net (code "17") (name "IO{slash}BOOT") (class "Default")
      (node (ref "BOOT_BUTTON") (pin "3") (pinfunction "3_3") (pintype "passive"))
      (node (ref "BOOT_BUTTON") (pin "4") (pinfunction "4_4") (pintype "passive"))
      (node (ref "C6") (pin "1") (pinfunction "1_1") (pintype "passive"))
      (node (ref "R_BOOT") (pin "1") (pinfunction "1_1") (pintype "passive"))
      (node (ref "U2") (pin "15") (pinfunction "IO9_15") (pintype "bidirectional"))
    )
    (net (code "18") (name "IO{slash}CHANGE") (class "Default")
      (node (ref "C10") (pin "1") (pinfunction "1_1") (pintype "passive"))
      (node (ref "CHANGE_BUTTON") (pin "3") (pinfunction "3_3") (pintype "passive"))
      (node (ref "CHANGE_BUTTON") (pin "4") (pinfunction "4_4") (pintype "passive"))
      (node (ref "R_CHANGE") (pin "1") (pinfunction "1_1") (pintype "passive"))
      (node (ref "U2") (pin "23") (pinfunction "IO15_23") (pintype "bidirectional"))
    )
    (net (code "19") (name "MISO") (class "Default")
      (node (ref "D12") (pin "2") (pinfunction "2_2") (pintype "passive"))
      (node (ref "J4") (pin "P7") (pinfunction "DAT0_P7") (pintype "bidirectional"))
      (node (ref "R8") (pin "1") (pinfunction "1_1") (pintype "passive"))
      (node (ref "TP6") (pin "TP") (pinfunction "TP_TP") (pintype "input"))
      (node (ref "U1") (pin "2") (pinfunction "DO(IO1)_2") (pintype "bidirectional"))
      (node (ref "U2") (pin "27") (pinfunction "IO2_27") (pintype "bidirectional"))
    )
    (net (code "20") (name "MOSI") (class "Default")
      (node (ref "D11") (pin "2") (pinfunction "2_2") (pintype "passive"))
      (node (ref "J1") (pin "14") (pinfunction "14_14") (pintype "bidirectional"))
      (node (ref "J4") (pin "P3") (pinfunction "CMD_P3") (pintype "bidirectional"))
      (node (ref "R7") (pin "1") (pinfunction "1_1") (pintype "passive"))
      (node (ref "TP7") (pin "TP") (pinfunction "TP_TP") (pintype "input"))
      (node (ref "U1") (pin "5") (pinfunction "DI(IO0)_5") (pintype "bidirectional"))
      (node (ref "U2") (pin "7") (pinfunction "IO7_7") (pintype "bidirectional"))
    )
    (net (code "21") (name "Net-(CHG_LED-PadC)") (class "Default")
      (node (ref "CHG_LED") (pin "C") (pinfunction "C_C") (pintype "passive"))
      (node (ref "R1_BAT") (pin "1") (pinfunction "1_1") (pintype "passive"))
    )
    (net (code "22") (name "Net-(D2-CATHODE)") (class "Default")
      (node (ref "C1_BAT1") (pin "1") (pinfunction "1_1") (pintype "passive"))
      (node (ref "D2") (pin "1") (pinfunction "CATHODE_1") (pintype "bidirectional"))
      (node (ref "IC4") (pin "1") (pinfunction "VIN_1") (pintype "bidirectional"))
      (node (ref "IC4") (pin "3") (pinfunction "CE_3") (pintype "bidirectional"))
      (node (ref "Q1") (pin "2") (pinfunction "S_2") (pintype "bidirectional"))
    )
    (net (code "23") (name "Net-(D3-A)") (class "Default")
      (node (ref "C4") (pin "1") (pinfunction "1_1") (pintype "passive"))
      (node (ref "D3") (pin "2") (pinfunction "A_2") (pintype "bidirectional"))
      (node (ref "D4") (pin "1") (pinfunction "K_1") (pintype "bidirectional"))
    )
    (net (code "24") (name "Net-(D7-CATHODE)") (class "Default")
      (node (ref "D7") (pin "1") (pinfunction "CATHODE_1") (pintype "bidirectional"))
      (node (ref "R_CAPACITOR") (pin "2") (pinfunction "2_2") (pintype "passive"))
    )
    (net (code "25") (name "Net-(EPD_C1-Pad2)") (class "Default")
      (node (ref "EPD_C1") (pin "2") (pinfunction "2_2") (pintype "passive"))
      (node (ref "J1") (pin "4") (pinfunction "4_4") (pintype "bidirectional"))
    )
    (net (code "26") (name "Net-(EPD_C2-Pad2)") (class "Default")
      (node (ref "EPD_C2") (pin "2") (pinfunction "2_2") (pintype "passive"))
      (node (ref "J1") (pin "5") (pinfunction "5_5") (pintype "bidirectional"))
    )
    (net (code "27") (name "Net-(EPD_C6-Pad2)") (class "Default")
      (node (ref "EPD_C6") (pin "2") (pinfunction "2_2") (pintype "passive"))
      (node (ref "J1") (pin "18") (pinfunction "18_18") (pintype "bidirectional"))
    )
    (net (code "28") (name "Net-(EPD_C7-Pad2)") (class "Default")
      (node (ref "EPD_C7") (pin "2") (pinfunction "2_2") (pintype "passive"))
      (node (ref "J1") (pin "19") (pinfunction "19_19") (pintype "bidirectional"))
    )
    (net (code "29") (name "Net-(EPD_C8-Pad2)") (class "Default")
      (node (ref "EPD_C8") (pin "2") (pinfunction "2_2") (pintype "passive"))
      (node (ref "J1") (pin "20") (pinfunction "20_20") (pintype "bidirectional"))
    )
    (net (code "30") (name "Net-(EPD_C10-Pad2)") (class "Default")
      (node (ref "EPD_C10") (pin "2") (pinfunction "2_2") (pintype "passive"))
      (node (ref "J1") (pin "22") (pinfunction "22_22") (pintype "bidirectional"))
    )
    (net (code "31") (name "Net-(EPD_C12-Pad2)") (class "Default")
      (node (ref "EPD_C12") (pin "2") (pinfunction "2_2") (pintype "passive"))
      (node (ref "J1") (pin "24") (pinfunction "24_24") (pintype "bidirectional"))
    )
    (net (code "32") (name "Net-(IC1-CT)") (class "Default")
      (node (ref "C_DELAY") (pin "1") (pinfunction "1_1") (pintype "passive"))
      (node (ref "IC1") (pin "5") (pinfunction "CT_5") (pintype "bidirectional"))
    )
    (net (code "33") (name "Net-(J2-PadA5)") (class "Default")
      (node (ref "J2") (pin "A5") (pinfunction "A5_A5") (pintype "bidirectional"))
      (node (ref "R2-USB1") (pin "2") (pinfunction "2_2") (pintype "passive"))
    )
    (net (code "34") (name "Net-(J2-PadB5)") (class "Default")
      (node (ref "J2") (pin "B5") (pinfunction "B5_B5") (pintype "bidirectional"))
      (node (ref "R2-USB2") (pin "2") (pinfunction "2_2") (pintype "passive"))
    )
    (net (code "35") (name "Net-(MCP73831-PROG)") (class "Default")
      (node (ref "MCP73831") (pin "5") (pinfunction "PROG_5") (pintype "input"))
      (node (ref "R2_BAT") (pin "2") (pinfunction "2_2") (pintype "passive"))
    )
    (net (code "36") (name "Net-(MCP73831-STAT)") (class "Default")
      (node (ref "MCP73831") (pin "1") (pinfunction "STAT_1") (pintype "output"))
      (node (ref "R1_BAT") (pin "2") (pinfunction "2_2") (pintype "passive"))
    )
    (net (code "37") (name "PREVGH") (class "Default")
      (node (ref "D5") (pin "1") (pinfunction "K_1") (pintype "bidirectional"))
      (node (ref "EPD_C9") (pin "2") (pinfunction "2_2") (pintype "passive"))
      (node (ref "J1") (pin "21") (pinfunction "21_21") (pintype "bidirectional"))
    )
    (net (code "38") (name "PREVGL") (class "Default")
      (node (ref "D4") (pin "2") (pinfunction "A_2") (pintype "bidirectional"))
      (node (ref "EPD_C11") (pin "2") (pinfunction "2_2") (pintype "passive"))
      (node (ref "J1") (pin "23") (pinfunction "23_23") (pintype "bidirectional"))
    )
    (net (code "39") (name "RESE") (class "Default")
      (node (ref "J1") (pin "3") (pinfunction "3_3") (pintype "bidirectional"))
      (node (ref "Q3") (pin "2") (pinfunction "S_2") (pintype "bidirectional"))
      (node (ref "R3") (pin "2") (pinfunction "2_2") (pintype "passive"))
    )
    (net (code "40") (name "RESE'") (class "Default")
      (node (ref "R1") (pin "2") (pinfunction "2_2") (pintype "passive"))
      (node (ref "R3") (pin "1") (pinfunction "1_1") (pintype "passive"))
      (node (ref "SJ1") (pin "2") (pinfunction "2_2") (pintype "passive"))
    )
    (net (code "41") (name "RESET") (class "Default")
      (node (ref "C5") (pin "1") (pinfunction "1_1") (pintype "passive"))
      (node (ref "IC1") (pin "1") (pinfunction "VOUT_1") (pintype "bidirectional"))
      (node (ref "RESET_BUTTON") (pin "3") (pinfunction "3_3") (pintype "passive"))
      (node (ref "RESET_BUTTON") (pin "4") (pinfunction "4_4") (pintype "passive"))
      (node (ref "R_RESET") (pin "1") (pinfunction "1_1") (pintype "passive"))
      (node (ref "U2") (pin "3") (pinfunction "EN_3") (pintype "input"))
    )
    (net (code "42") (name "RTC_RST") (class "Default")
      (node (ref "U2") (pin "16") (pinfunction "IO18_16") (pintype "bidirectional"))
      (node (ref "U3") (pin "4") (pinfunction "~{RST}_4") (pintype "input"))
    )
    (net (code "43") (name "RX") (class "Default")
      (node (ref "TP2") (pin "TP") (pinfunction "TP_TP") (pintype "input"))
      (node (ref "U2") (pin "24") (pinfunction "RXD0/GPIO17_24") (pintype "bidirectional"))
    )
    (net (code "44") (name "SCK") (class "Default")
      (node (ref "D10") (pin "2") (pinfunction "2_2") (pintype "passive"))
      (node (ref "J1") (pin "13") (pinfunction "13_13") (pintype "bidirectional"))
      (node (ref "J4") (pin "P5") (pinfunction "CLK_P5") (pintype "bidirectional"))
      (node (ref "R6") (pin "1") (pinfunction "1_1") (pintype "passive"))
      (node (ref "TP8") (pin "TP") (pinfunction "TP_TP") (pintype "input"))
      (node (ref "U1") (pin "6") (pinfunction "CLK_6") (pintype "input"))
      (node (ref "U2") (pin "6") (pinfunction "IO6_6") (pintype "bidirectional"))
    )
    (net (code "45") (name "SCL") (class "Default")
      (node (ref "J3") (pin "4") (pinfunction "4_4") (pintype "passive"))
      (node (ref "R_CL2") (pin "1") (pinfunction "1_1") (pintype "passive"))
      (node (ref "SENSOR2") (pin "4") (pinfunction "SCK_4") (pintype "input"))
      (node (ref "U2") (pin "20") (pinfunction "IO22_20") (pintype "bidirectional"))
      (node (ref "U3") (pin "16") (pinfunction "SCL_16") (pintype "input"))
      (node (ref "U4") (pin "7") (pinfunction "SCL_7") (pintype "input"))
    )
    (net (code "46") (name "SDA") (class "Default")
      (node (ref "J3") (pin "3") (pinfunction "3_3") (pintype "passive"))
      (node (ref "R_CL3") (pin "1") (pinfunction "1_1") (pintype "passive"))
      (node (ref "SENSOR2") (pin "3") (pinfunction "SDI_3") (pintype "bidirectional"))
      (node (ref "U2") (pin "19") (pinfunction "IO21_19") (pintype "bidirectional"))
      (node (ref "U3") (pin "15") (pinfunction "SDA_15") (pintype "bidirectional"))
      (node (ref "U4") (pin "8") (pinfunction "SDA_8") (pintype "bidirectional"))
    )
    (net (code "47") (name "SRC") (class "Default")
      (node (ref "C4") (pin "2") (pinfunction "2_2") (pintype "passive"))
      (node (ref "D5") (pin "2") (pinfunction "A_2") (pintype "bidirectional"))
      (node (ref "L1") (pin "1") (pinfunction "1_1") (pintype "passive"))
      (node (ref "Q3") (pin "3") (pinfunction "D_3") (pintype "bidirectional"))
    )
    (net (code "48") (name "SS_SD") (class "Default")
      (node (ref "D8") (pin "2") (pinfunction "2_2") (pintype "passive"))
      (node (ref "J4") (pin "P2") (pinfunction "CD/DAT3_P2") (pintype "bidirectional"))
      (node (ref "R10") (pin "1") (pinfunction "1_1") (pintype "passive"))
      (node (ref "U2") (pin "4") (pinfunction "IO4_4") (pintype "bidirectional"))
    )
    (net (code "49") (name "TX") (class "Default")
      (node (ref "TP1") (pin "TP") (pinfunction "TP_TP") (pintype "input"))
      (node (ref "U2") (pin "25") (pinfunction "TXD0/GPIO16_25") (pintype "bidirectional"))
    )
    (net (code "50") (name "USB_D+") (class "Default")
      (node (ref "D1") (pin "4") (pinfunction "I/O2_2_4") (pintype "bidirectional"))
      (node (ref "U2") (pin "14") (pinfunction "IO13_14") (pintype "bidirectional"))
    )
    (net (code "51") (name "USB_D-") (class "Default")
      (node (ref "D1") (pin "6") (pinfunction "I/O1_2_6") (pintype "bidirectional"))
      (node (ref "U2") (pin "13") (pinfunction "IO12_13") (pintype "bidirectional"))
    )
    (net (code "52") (name "VBAT") (class "Default")
      (node (ref "C2_BAT") (pin "1") (pinfunction "1_1") (pintype "passive"))
      (node (ref "MCP73831") (pin "3") (pinfunction "VBAT_3") (pintype "power_in"))
      (node (ref "Q1") (pin "3") (pinfunction "D_3") (pintype "bidirectional"))
      (node (ref "TP3") (pin "TP") (pinfunction "TP_TP") (pintype "input"))
      (node (ref "U4") (pin "2") (pinfunction "CELL_2") (pintype "power_in"))
      (node (ref "U4") (pin "3") (pinfunction "VDD_3") (pintype "power_in"))
    )
    (net (code "53") (name "VBUS") (class "Default")
      (node (ref "C1_BAT") (pin "1") (pinfunction "1_1") (pintype "passive"))
      (node (ref "C4_USB") (pin "1") (pinfunction "1_1") (pintype "passive"))
      (node (ref "C5_USB") (pin "1") (pinfunction "1_1") (pintype "passive"))
      (node (ref "CHG_LED") (pin "A") (pinfunction "A_A") (pintype "passive"))
      (node (ref "D1") (pin "2") (pinfunction "GND_2") (pintype "bidirectional"))
      (node (ref "D2") (pin "2") (pinfunction "ANODE_2") (pintype "bidirectional"))
      (node (ref "MCP73831") (pin "4") (pinfunction "VIN_4") (pintype "power_in"))
      (node (ref "PFMF.050.1") (pin "2") (pinfunction "2_2") (pintype "passive"))
      (node (ref "Q1") (pin "1") (pinfunction "G_1") (pintype "bidirectional"))
      (node (ref "R1_PWRUSB") (pin "2") (pinfunction "2_2") (pintype "passive"))
      (node (ref "TP14") (pin "TP") (pinfunction "TP_TP") (pintype "input"))
    )
    (net (code "54") (name "VRTC") (class "Default")
      (node (ref "C10_SUPERCAP") (pin "1") (pinfunction "1_1") (pintype "passive"))
      (node (ref "C8") (pin "1") (pinfunction "1_1") (pintype "passive"))
      (node (ref "R_CAPACITOR") (pin "1") (pinfunction "1_1") (pintype "passive"))
      (node (ref "U3") (pin "14") (pinfunction "VBAT_14") (pintype "power_in"))
    )
    (net (code "55") (name "VUSB") (class "Default")
      (node (ref "J2") (pin "A4") (pinfunction "A4_A4") (pintype "bidirectional"))
      (node (ref "J2") (pin "A9") (pinfunction "A9_A9") (pintype "bidirectional"))
      (node (ref "J2") (pin "B4") (pinfunction "B4_B4") (pintype "bidirectional"))
      (node (ref "J2") (pin "B9") (pinfunction "B9_B9") (pintype "bidirectional"))
      (node (ref "PFMF.050.1") (pin "1") (pinfunction "1_1") (pintype "passive"))
    )
    (net (code "56") (name "unconnected-(IC1-NC-Pad4)") (class "Default")
      (node (ref "IC1") (pin "4") (pinfunction "NC_4") (pintype "no_connect"))
    )
    (net (code "57") (name "unconnected-(IC4-NC-Pad4)") (class "Default")
      (node (ref "IC4") (pin "4") (pinfunction "NC_4") (pintype "no_connect"))
    )
    (net (code "58") (name "unconnected-(J1-Pad1)") (class "Default")
      (node (ref "J1") (pin "1") (pinfunction "1_1") (pintype "bidirectional"))
    )
    (net (code "59") (name "unconnected-(J1-Pad6)") (class "Default")
      (node (ref "J1") (pin "6") (pinfunction "6_6") (pintype "bidirectional"))
    )
    (net (code "60") (name "unconnected-(J1-Pad7)") (class "Default")
      (node (ref "J1") (pin "7") (pinfunction "7_7") (pintype "bidirectional"))
    )
    (net (code "61") (name "unconnected-(J2-PadA8)") (class "Default")
      (node (ref "J2") (pin "A8") (pinfunction "A8_A8") (pintype "bidirectional"))
    )
    (net (code "62") (name "unconnected-(J2-PadB8)") (class "Default")
      (node (ref "J2") (pin "B8") (pinfunction "B8_B8") (pintype "bidirectional"))
    )
    (net (code "63") (name "unconnected-(J4-DAT1-PadP8)") (class "Default")
      (node (ref "J4") (pin "P8") (pinfunction "DAT1_P8") (pintype "bidirectional"))
    )
    (net (code "64") (name "unconnected-(J4-DAT2-PadP1)") (class "Default")
      (node (ref "J4") (pin "P1") (pinfunction "DAT2_P1") (pintype "bidirectional"))
    )
    (net (code "65") (name "unconnected-(J4-DETECTION_1-PadS1)") (class "Default")
      (node (ref "J4") (pin "S1") (pinfunction "DETECTION_1_S1") (pintype "bidirectional"))
    )
    (net (code "66") (name "unconnected-(J4-DETECTION_2-PadS2)") (class "Default")
      (node (ref "J4") (pin "S2") (pinfunction "DETECTION_2_S2") (pintype "bidirectional"))
    )
    (net (code "67") (name "unconnected-(U2-NC-Pad22)") (class "Default")
      (node (ref "U2") (pin "22") (pinfunction "NC_22") (pintype "no_connect"))
    )
    (net (code "68") (name "unconnected-(U4-~{ALERT}-Pad5)") (class "Default")
      (node (ref "U4") (pin "5") (pinfunction "~{ALERT}_5") (pintype "output"))
    )
  )
)
